# mpu6050.net
KiCad netlist of a schematic drawn in EAGLE
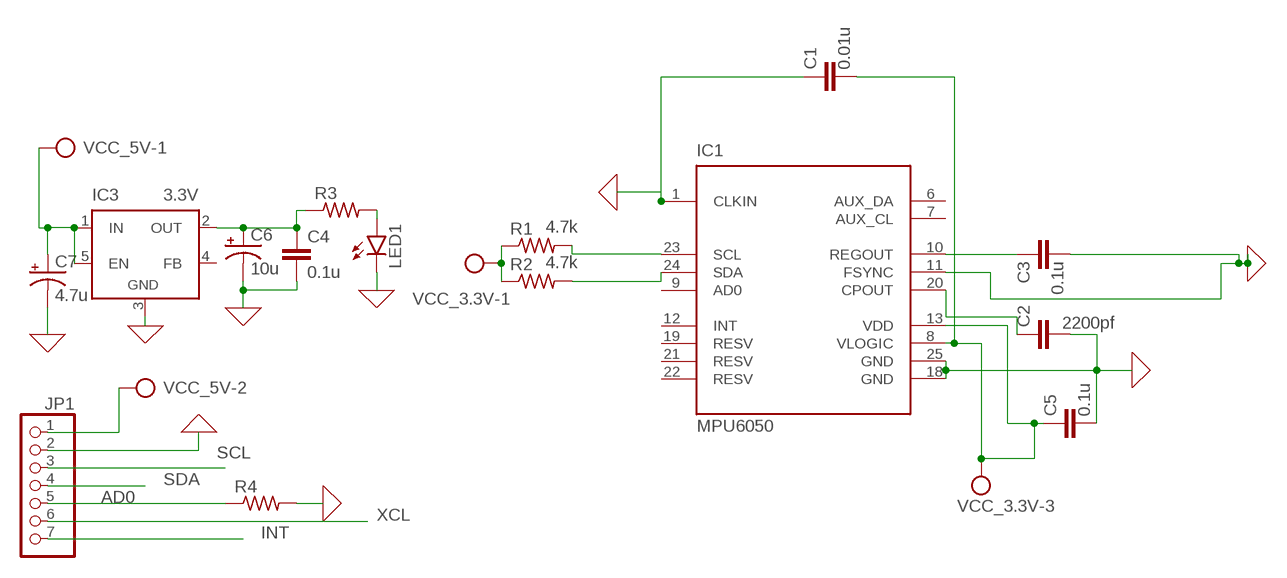
[diagram p0: schematic, sheet 1]

(export (version "E")
  (design (tool "Eeschema 10.0.6"))
  (components
    (comp (ref "C1")
      (value "0.01u")
      (footprint "eagle-import:C025-024X044")
      (libsource (lib "eagle-import") (part "C-EU025-024X044"))
    )
    (comp (ref "C2")
      (value "2200pf")
      (footprint "eagle-import:C025-024X044")
      (libsource (lib "eagle-import") (part "C-EU025-024X044"))
    )
    (comp (ref "C3")
      (value "0.1u")
      (footprint "eagle-import:C025-024X044")
      (libsource (lib "eagle-import") (part "C-EU025-024X044"))
    )
    (comp (ref "C4")
      (value "0.1u")
      (footprint "eagle-import:HPC0201")
      (libsource (lib "eagle-import") (part "C-EUHPC0201"))
    )
    (comp (ref "C5")
      (value "0.1u")
      (footprint "eagle-import:C025-024X044")
      (libsource (lib "eagle-import") (part "C-EU025-024X044"))
    )
    (comp (ref "C6")
      (value "10u")
      (footprint "eagle-import:E2,5-7")
      (libsource (lib "eagle-import") (part "CPOL-USE2.5-7"))
    )
    (comp (ref "C7")
      (value "4.7u")
      (footprint "eagle-import:E2,5-7")
      (libsource (lib "eagle-import") (part "CPOL-USE2.5-7"))
    )
    (comp (ref "IC1")
      (value "MPU6050")
      (footprint "eagle-import:QFN50P400X400X95-25T265X275N")
      (libsource (lib "eagle-import") (part "MPU6050"))
    )
    (comp (ref "IC3")
      (value "3.3V")
      (footprint "eagle-import:TO220-52")
      (libsource (lib "eagle-import") (part "LM2596TH"))
    )
    (comp (ref "JP1")
      (value "PINHD-1X7/90")
      (footprint "eagle-import:1X07_90")
      (libsource (lib "eagle-import") (part "PINHD-1X7/90"))
    )
    (comp (ref "LED1")
      (value "LED3MM")
      (footprint "eagle-import:LED3MM")
      (libsource (lib "eagle-import") (part "LED3MM"))
    )
    (comp (ref "R1")
      (value "4.7k")
      (footprint "eagle-import:0207_5V")
      (libsource (lib "eagle-import") (part "R-US_0207/5V"))
    )
    (comp (ref "R2")
      (value "4.7k")
      (footprint "eagle-import:0207_5V")
      (libsource (lib "eagle-import") (part "R-US_0207/5V"))
    )
    (comp (ref "R3")
      (value "R-US_0207/5V")
      (footprint "eagle-import:0207_5V")
      (libsource (lib "eagle-import") (part "R-US_0207/5V"))
    )
    (comp (ref "R4")
      (value "R-US_0207/5V")
      (footprint "eagle-import:0207_5V")
      (libsource (lib "eagle-import") (part "R-US_0207/5V"))
    )
    (comp (ref "VCC_3.3V")
      (value "AK300/3")
      (footprint "eagle-import:AK300_3")
      (libsource (lib "eagle-import") (part "AK300/3"))
    )
    (comp (ref "VCC_5V")
      (value "AK300/2")
      (footprint "eagle-import:AK300_2")
      (libsource (lib "eagle-import") (part "AK300/2"))
    )
  )
  (nets
    (net (code "1") (name "/AD0") (class "Default")
      (node (ref "JP1") (pin "5") (pinfunction "5_5") (pintype "passive"))
      (node (ref "R4") (pin "1") (pinfunction "1_1") (pintype "passive"))
    )
    (net (code "2") (name "/INT") (class "Default")
      (node (ref "JP1") (pin "7") (pinfunction "7_7") (pintype "passive"))
    )
    (net (code "3") (name "/SCL") (class "Default")
      (node (ref "JP1") (pin "3") (pinfunction "3_3") (pintype "passive"))
    )
    (net (code "4") (name "/SDA") (class "Default")
      (node (ref "JP1") (pin "4") (pinfunction "4_4") (pintype "passive"))
    )
    (net (code "5") (name "/XCL") (class "Default")
      (node (ref "JP1") (pin "6") (pinfunction "6_6") (pintype "passive"))
    )
    (net (code "6") (name "GND") (class "Default")
      (node (ref "C1") (pin "1") (pinfunction "1_1") (pintype "passive"))
      (node (ref "C2") (pin "2") (pinfunction "2_2") (pintype "passive"))
      (node (ref "C3") (pin "2") (pinfunction "2_2") (pintype "passive"))
      (node (ref "C4") (pin "2") (pinfunction "2_2") (pintype "passive"))
      (node (ref "C5") (pin "2") (pinfunction "2_2") (pintype "passive"))
      (node (ref "C6") (pin "-") (pinfunction "-_-") (pintype "passive"))
      (node (ref "C7") (pin "-") (pinfunction "-_-") (pintype "passive"))
      (node (ref "IC1") (pin "1") (pinfunction "CLKIN_1") (pintype "input"))
      (node (ref "IC1") (pin "11") (pinfunction "FSYNC_11") (pintype "input"))
      (node (ref "IC1") (pin "18") (pinfunction "GND_18") (pintype "power_in"))
      (node (ref "IC1") (pin "25") (pinfunction "GND_25") (pintype "power_in"))
      (node (ref "IC3") (pin "3") (pinfunction "GND_3") (pintype "power_in"))
      (node (ref "JP1") (pin "2") (pinfunction "2_2") (pintype "passive"))
      (node (ref "LED1") (pin "K") (pinfunction "C_K") (pintype "passive"))
      (node (ref "R4") (pin "2") (pinfunction "2_2") (pintype "passive"))
    )
    (net (code "7") (name "Net-(IC1A-CPOUT)") (class "Default")
      (node (ref "C2") (pin "1") (pinfunction "1_1") (pintype "passive"))
      (node (ref "IC1") (pin "20") (pinfunction "CPOUT_20") (pintype "output"))
    )
    (net (code "8") (name "Net-(IC1A-REGOUT)") (class "Default")
      (node (ref "C3") (pin "1") (pinfunction "1_1") (pintype "passive"))
      (node (ref "IC1") (pin "10") (pinfunction "REGOUT_10") (pintype "output"))
    )
    (net (code "9") (name "Net-(IC1A-SCL)") (class "Default")
      (node (ref "IC1") (pin "23") (pinfunction "SCL_23") (pintype "input"))
      (node (ref "R1") (pin "2") (pinfunction "2_2") (pintype "passive"))
    )
    (net (code "10") (name "Net-(IC1A-SDA)") (class "Default")
      (node (ref "IC1") (pin "24") (pinfunction "SDA_24") (pintype "bidirectional"))
      (node (ref "R2") (pin "2") (pinfunction "2_2") (pintype "passive"))
    )
    (net (code "11") (name "Net-(IC1A-VDD)") (class "Default")
      (node (ref "C1") (pin "2") (pinfunction "2_2") (pintype "passive"))
      (node (ref "C5") (pin "1") (pinfunction "1_1") (pintype "passive"))
      (node (ref "IC1") (pin "13") (pinfunction "VDD_13") (pintype "power_in"))
      (node (ref "IC1") (pin "8") (pinfunction "VLOGIC_8") (pintype "power_in"))
      (node (ref "VCC_3.3V") (pin "3") (pinfunction "KL_3") (pintype "passive"))
    )
    (net (code "12") (name "Net-(IC3-EN)") (class "Default")
      (node (ref "C7") (pin "+") (pinfunction "+_+") (pintype "passive"))
      (node (ref "IC3") (pin "1") (pinfunction "IN_1") (pintype "input"))
      (node (ref "IC3") (pin "5") (pinfunction "EN_5") (pintype "input"))
      (node (ref "VCC_5V") (pin "1") (pinfunction "KL_1") (pintype "passive"))
    )
    (net (code "13") (name "Net-(IC3-OUT)") (class "Default")
      (node (ref "C4") (pin "1") (pinfunction "1_1") (pintype "passive"))
      (node (ref "C6") (pin "+") (pinfunction "+_+") (pintype "passive"))
      (node (ref "IC3") (pin "2") (pinfunction "OUT_2") (pintype "output"))
      (node (ref "R3") (pin "1") (pinfunction "1_1") (pintype "passive"))
    )
    (net (code "14") (name "Net-(LED1-PadA)") (class "Default")
      (node (ref "LED1") (pin "A") (pinfunction "A_A") (pintype "passive"))
      (node (ref "R3") (pin "2") (pinfunction "2_2") (pintype "passive"))
    )
    (net (code "15") (name "Net-(VCC_3.3VA-KL)") (class "Default")
      (node (ref "R1") (pin "1") (pinfunction "1_1") (pintype "passive"))
      (node (ref "R2") (pin "1") (pinfunction "1_1") (pintype "passive"))
      (node (ref "VCC_3.3V") (pin "1") (pinfunction "KL_1") (pintype "passive"))
    )
    (net (code "16") (name "Net-(VCC_5VB-KL)") (class "Default")
      (node (ref "JP1") (pin "1") (pinfunction "1_1") (pintype "passive"))
      (node (ref "VCC_5V") (pin "2") (pinfunction "KL_2") (pintype "passive"))
    )
    (net (code "17") (name "unconnected-(IC1A-AD0-Pad9)") (class "Default")
      (node (ref "IC1") (pin "9") (pinfunction "AD0_9") (pintype "input"))
    )
    (net (code "18") (name "unconnected-(IC1A-AUX_CL-Pad7)") (class "Default")
      (node (ref "IC1") (pin "7") (pinfunction "AUX_CL_7") (pintype "bidirectional"))
    )
    (net (code "19") (name "unconnected-(IC1A-AUX_DA-Pad6)") (class "Default")
      (node (ref "IC1") (pin "6") (pinfunction "AUX_DA_6") (pintype "bidirectional"))
    )
    (net (code "20") (name "unconnected-(IC1A-INT-Pad12)") (class "Default")
      (node (ref "IC1") (pin "12") (pinfunction "INT_12") (pintype "open_collector"))
    )
    (net (code "21") (name "unconnected-(IC1A-RESV-Pad19)") (class "Default")
      (node (ref "IC1") (pin "19") (pinfunction "RESV_19") (pintype "passive"))
    )
    (net (code "22") (name "unconnected-(IC1A-RESV-Pad21)") (class "Default")
      (node (ref "IC1") (pin "21") (pinfunction "RESV_21") (pintype "passive"))
    )
    (net (code "23") (name "unconnected-(IC1A-RESV-Pad22)") (class "Default")
      (node (ref "IC1") (pin "22") (pinfunction "RESV_22") (pintype "passive"))
    )
    (net (code "24") (name "unconnected-(IC3-FB-Pad4)") (class "Default")
      (node (ref "IC3") (pin "4") (pinfunction "FB_4") (pintype "input"))
    )
  )
)
